# PiTopUSBHub.net
KiCad netlist of a schematic drawn in Altium Designer
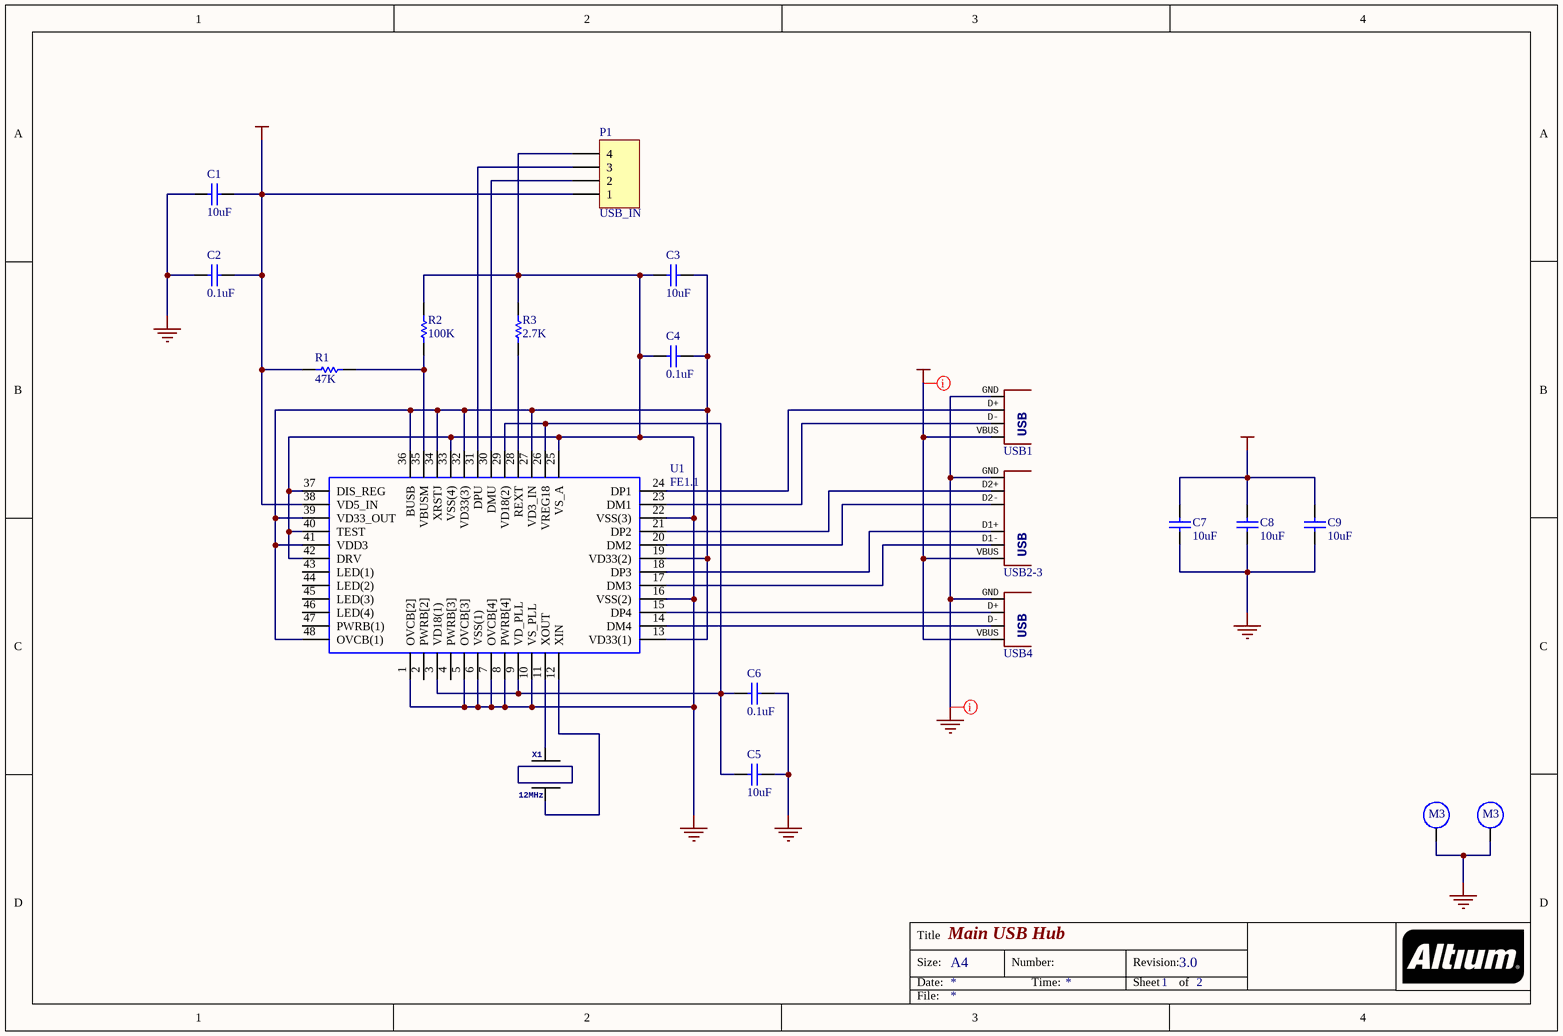
[diagram p0: PiTopUSBHub.SchDoc]

(export (version "E")
  (design (tool "Eeschema 10.0.6"))
  (components
    (comp (ref "C1")
      (value "10uF")
      (footprint "C0805")
      (description "Ceramic Chip Capacitor - Standard")
      (fields (field (name "Comment") "C0805") (field (name "PUBLISHER") "Altium Limited"))
      (libsource (lib "KEMET Chip Capacitor") (part "C0805"))
    )
    (comp (ref "C2")
      (value "0.1uF")
      (footprint "C0805")
      (description "Ceramic Chip Capacitor - Standard")
      (fields (field (name "Comment") "C0805") (field (name "PUBLISHER") "Altium Limited"))
      (libsource (lib "KEMET Chip Capacitor") (part "C0805"))
    )
    (comp (ref "C3")
      (value "10uF")
      (footprint "C0805")
      (description "Ceramic Chip Capacitor - Standard")
      (fields (field (name "Comment") "C0805") (field (name "PUBLISHER") "Altium Limited"))
      (libsource (lib "KEMET Chip Capacitor") (part "C0805"))
    )
    (comp (ref "C4")
      (value "0.1uF")
      (footprint "C0805")
      (description "Ceramic Chip Capacitor - Standard")
      (fields (field (name "Comment") "C0805") (field (name "PUBLISHER") "Altium Limited"))
      (libsource (lib "KEMET Chip Capacitor") (part "C0805"))
    )
    (comp (ref "C5")
      (value "10uF")
      (footprint "C0805")
      (description "Ceramic Chip Capacitor - Standard")
      (fields (field (name "Comment") "C0805") (field (name "PUBLISHER") "Altium Limited"))
      (libsource (lib "KEMET Chip Capacitor") (part "C0805"))
    )
    (comp (ref "C6")
      (value "0.1uF")
      (footprint "C0805")
      (description "Ceramic Chip Capacitor - Standard")
      (fields (field (name "Comment") "C0805") (field (name "PUBLISHER") "Altium Limited"))
      (libsource (lib "KEMET Chip Capacitor") (part "C0805"))
    )
    (comp (ref "C7")
      (value "10uF")
      (footprint "C0805")
      (description "Ceramic Chip Capacitor - Standard")
      (fields (field (name "Comment") "C0805") (field (name "PUBLISHER") "Altium Limited"))
      (libsource (lib "KEMET Chip Capacitor") (part "C0805"))
    )
    (comp (ref "C8")
      (value "10uF")
      (footprint "C0805")
      (description "Ceramic Chip Capacitor - Standard")
      (fields (field (name "Comment") "C0805") (field (name "PUBLISHER") "Altium Limited"))
      (libsource (lib "KEMET Chip Capacitor") (part "C0805"))
    )
    (comp (ref "C9")
      (value "10uF")
      (footprint "C0805")
      (description "Ceramic Chip Capacitor - Standard")
      (fields (field (name "Comment") "C0805") (field (name "PUBLISHER") "Altium Limited"))
      (libsource (lib "KEMET Chip Capacitor") (part "C0805"))
    )
    (comp (ref "H1") (value "M3") (footprint "M3") (libsource (lib "lib") (part "M3")))
    (comp (ref "H2") (value "M3") (footprint "M3") (libsource (lib "lib") (part "M3")))
    (comp (ref "P1")
      (value "USB_IN")
      (footprint "HDR1X4")
      (description "Header, 4-Pin")
      (fields (field (name "PUBLISHER") "Altium Limited"))
      (libsource (lib "Miscellaneous Connectors") (part "Header 4"))
    )
    (comp (ref "R1")
      (value "47K")
      (footprint "R0805")
      (fields (field (name "PUBLISHER") "Altium Limited"))
      (libsource (lib "lib") (part "R0805"))
    )
    (comp (ref "R2")
      (value "100K")
      (footprint "R0805")
      (fields (field (name "PUBLISHER") "Altium Limited"))
      (libsource (lib "lib") (part "R0805"))
    )
    (comp (ref "R3")
      (value "2.7K")
      (footprint "R0805")
      (fields (field (name "PUBLISHER") "Altium Limited"))
      (libsource (lib "lib") (part "R0805"))
    )
    (comp (ref "U1")
      (value "FE1.1")
      (footprint "LQFP48")
      (description "USB 2.0 HIGH SPEED 4-PORT HUB CONTROLLER")
      (libsource (lib "lib") (part "FE1.1"))
    )
    (comp (ref "USB1")
      (value "USBA-PTH")
      (footprint "USB-A-F-PTH")
      (fields (field (name "USB") "USB"))
      (libsource (lib "lib") (part "USBA-PTH"))
    )
    (comp (ref "USB2-3")
      (value "USBA2x-PTH")
      (footprint "USB-A-2x-F-PTH")
      (fields (field (name "USB") "USB"))
      (libsource (lib "lib") (part "USBA2x-PTH"))
    )
    (comp (ref "USB4")
      (value "USBA-PTH")
      (footprint "USB-A-F-PTH")
      (fields (field (name "USB") "USB"))
      (libsource (lib "lib") (part "USBA-PTH"))
    )
    (comp (ref "X1")
      (value "12MHz")
      (footprint "XTAL_G5032")
      (description "PTH: ...   SMD: ...   Cylinder: CMR200T-32.768KDZBT")
      (libsource (lib "lib") (part "CRYSTALHC49UP"))
    )
  )
  (nets
    (net (code "1") (name "GND") (class "Default")
      (node (ref "C1") (pin "2") (pinfunction "2_2") (pintype "passive"))
      (node (ref "C2") (pin "2") (pinfunction "2_2") (pintype "passive"))
      (node (ref "C3") (pin "2") (pinfunction "2_2") (pintype "passive"))
      (node (ref "C4") (pin "2") (pinfunction "2_2") (pintype "passive"))
      (node (ref "C5") (pin "2") (pinfunction "2_2") (pintype "passive"))
      (node (ref "C6") (pin "2") (pinfunction "2_2") (pintype "passive"))
      (node (ref "C7") (pin "2") (pinfunction "2_2") (pintype "passive"))
      (node (ref "C8") (pin "2") (pinfunction "2_2") (pintype "passive"))
      (node (ref "C9") (pin "2") (pinfunction "2_2") (pintype "passive"))
      (node (ref "H1") (pin "1") (pinfunction "1_1") (pintype "passive"))
      (node (ref "H2") (pin "1") (pinfunction "1_1") (pintype "passive"))
      (node (ref "P1") (pin "4") (pinfunction "4_4") (pintype "passive"))
      (node (ref "R2") (pin "1") (pinfunction "1_1") (pintype "passive"))
      (node (ref "R3") (pin "2") (pinfunction "2_2") (pintype "passive"))
      (node (ref "U1") (pin "1") (pinfunction "OVCB[2]_1") (pintype "passive"))
      (node (ref "U1") (pin "10") (pinfunction "VS_PLL_10") (pintype "passive"))
      (node (ref "U1") (pin "16") (pinfunction "VSS(2)_16") (pintype "passive"))
      (node (ref "U1") (pin "22") (pinfunction "VSS(3)_22") (pintype "passive"))
      (node (ref "U1") (pin "25") (pinfunction "VS_A_25") (pintype "passive"))
      (node (ref "U1") (pin "33") (pinfunction "VSS(4)_33") (pintype "passive"))
      (node (ref "U1") (pin "37") (pinfunction "DIS_REG_37") (pintype "passive"))
      (node (ref "U1") (pin "40") (pinfunction "TEST_40") (pintype "passive"))
      (node (ref "U1") (pin "42") (pinfunction "DRV_42") (pintype "passive"))
      (node (ref "U1") (pin "5") (pinfunction "OVCB[3]_5") (pintype "passive"))
      (node (ref "U1") (pin "6") (pinfunction "VSS(1)_6") (pintype "passive"))
      (node (ref "U1") (pin "7") (pinfunction "OVCB[4]_7") (pintype "passive"))
      (node (ref "U1") (pin "8") (pinfunction "PWRB[4]_8") (pintype "passive"))
      (node (ref "USB1") (pin "GND") (pinfunction "GND_GND") (pintype "passive"))
      (node (ref "USB2-3") (pin "GND") (pinfunction "GND_GND") (pintype "passive"))
      (node (ref "USB4") (pin "GND") (pinfunction "GND_GND") (pintype "passive"))
    )
    (net (code "2") (name "Net-(U1-BUSB)") (class "Default")
      (node (ref "C3") (pin "1") (pinfunction "1_1") (pintype "passive"))
      (node (ref "C4") (pin "1") (pinfunction "1_1") (pintype "passive"))
      (node (ref "U1") (pin "13") (pinfunction "VD33(1)_13") (pintype "passive"))
      (node (ref "U1") (pin "19") (pinfunction "VD33(2)_19") (pintype "passive"))
      (node (ref "U1") (pin "27") (pinfunction "VD3_IN_27") (pintype "passive"))
      (node (ref "U1") (pin "32") (pinfunction "VD33(3)_32") (pintype "passive"))
      (node (ref "U1") (pin "34") (pinfunction "XRSTJ_34") (pintype "passive"))
      (node (ref "U1") (pin "36") (pinfunction "BUSB_36") (pintype "passive"))
      (node (ref "U1") (pin "39") (pinfunction "VD33_OUT_39") (pintype "passive"))
      (node (ref "U1") (pin "41") (pinfunction "VDD3_41") (pintype "passive"))
      (node (ref "U1") (pin "48") (pinfunction "OVCB(1)_48") (pintype "passive"))
    )
    (net (code "3") (name "Net-(U1-DM1)") (class "Default")
      (node (ref "U1") (pin "23") (pinfunction "DM1_23") (pintype "passive"))
      (node (ref "USB1") (pin "D-") (pinfunction "D-_D-") (pintype "passive"))
    )
    (net (code "4") (name "Net-(U1-DM2)") (class "Default")
      (node (ref "U1") (pin "20") (pinfunction "DM2_20") (pintype "passive"))
      (node (ref "USB2-3") (pin "D2-") (pinfunction "D2-_D2-") (pintype "passive"))
    )
    (net (code "5") (name "Net-(U1-DM3)") (class "Default")
      (node (ref "U1") (pin "17") (pinfunction "DM3_17") (pintype "passive"))
      (node (ref "USB2-3") (pin "D1-") (pinfunction "D1-_D1-") (pintype "passive"))
    )
    (net (code "6") (name "Net-(U1-DM4)") (class "Default")
      (node (ref "U1") (pin "14") (pinfunction "DM4_14") (pintype "passive"))
      (node (ref "USB4") (pin "D-") (pinfunction "D-_D-") (pintype "passive"))
    )
    (net (code "7") (name "Net-(U1-DMU)") (class "Default")
      (node (ref "P1") (pin "2") (pinfunction "2_2") (pintype "passive"))
      (node (ref "U1") (pin "30") (pinfunction "DMU_30") (pintype "passive"))
    )
    (net (code "8") (name "Net-(U1-DP1)") (class "Default")
      (node (ref "U1") (pin "24") (pinfunction "DP1_24") (pintype "passive"))
      (node (ref "USB1") (pin "D+") (pinfunction "D+_D+") (pintype "passive"))
    )
    (net (code "9") (name "Net-(U1-DP2)") (class "Default")
      (node (ref "U1") (pin "21") (pinfunction "DP2_21") (pintype "passive"))
      (node (ref "USB2-3") (pin "D2+") (pinfunction "D2+_D2+") (pintype "passive"))
    )
    (net (code "10") (name "Net-(U1-DP3)") (class "Default")
      (node (ref "U1") (pin "18") (pinfunction "DP3_18") (pintype "passive"))
      (node (ref "USB2-3") (pin "D1+") (pinfunction "D1+_D1+") (pintype "passive"))
    )
    (net (code "11") (name "Net-(U1-DP4)") (class "Default")
      (node (ref "U1") (pin "15") (pinfunction "DP4_15") (pintype "passive"))
      (node (ref "USB4") (pin "D+") (pinfunction "D+_D+") (pintype "passive"))
    )
    (net (code "12") (name "Net-(U1-DPU)") (class "Default")
      (node (ref "P1") (pin "3") (pinfunction "3_3") (pintype "passive"))
      (node (ref "U1") (pin "31") (pinfunction "DPU_31") (pintype "passive"))
    )
    (net (code "13") (name "Net-(U1-REXT)") (class "Default")
      (node (ref "R3") (pin "1") (pinfunction "1_1") (pintype "passive"))
      (node (ref "U1") (pin "28") (pinfunction "REXT_28") (pintype "passive"))
    )
    (net (code "14") (name "Net-(U1-VBUSM)") (class "Default")
      (node (ref "R1") (pin "2") (pinfunction "2_2") (pintype "passive"))
      (node (ref "R2") (pin "2") (pinfunction "2_2") (pintype "passive"))
      (node (ref "U1") (pin "35") (pinfunction "VBUSM_35") (pintype "passive"))
    )
    (net (code "15") (name "Net-(U1-VD18(1))") (class "Default")
      (node (ref "C5") (pin "1") (pinfunction "1_1") (pintype "passive"))
      (node (ref "C6") (pin "1") (pinfunction "1_1") (pintype "passive"))
      (node (ref "U1") (pin "26") (pinfunction "VREG18_26") (pintype "passive"))
      (node (ref "U1") (pin "29") (pinfunction "VD18(2)_29") (pintype "passive"))
      (node (ref "U1") (pin "3") (pinfunction "VD18(1)_3") (pintype "passive"))
      (node (ref "U1") (pin "9") (pinfunction "VD_PLL_9") (pintype "passive"))
    )
    (net (code "16") (name "Net-(U1-XIN)") (class "Default")
      (node (ref "U1") (pin "12") (pinfunction "XIN_12") (pintype "passive"))
      (node (ref "X1") (pin "1") (pinfunction "1_1") (pintype "passive"))
    )
    (net (code "17") (name "Net-(U1-XOUT)") (class "Default")
      (node (ref "U1") (pin "11") (pinfunction "XOUT_11") (pintype "passive"))
      (node (ref "X1") (pin "2") (pinfunction "2_2") (pintype "passive"))
    )
    (net (code "18") (name "VCC") (class "Default")
      (node (ref "C1") (pin "1") (pinfunction "1_1") (pintype "passive"))
      (node (ref "C2") (pin "1") (pinfunction "1_1") (pintype "passive"))
      (node (ref "C7") (pin "1") (pinfunction "1_1") (pintype "passive"))
      (node (ref "C8") (pin "1") (pinfunction "1_1") (pintype "passive"))
      (node (ref "C9") (pin "1") (pinfunction "1_1") (pintype "passive"))
      (node (ref "P1") (pin "1") (pinfunction "1_1") (pintype "passive"))
      (node (ref "R1") (pin "1") (pinfunction "1_1") (pintype "passive"))
      (node (ref "U1") (pin "38") (pinfunction "VD5_IN_38") (pintype "passive"))
      (node (ref "USB1") (pin "VBUS") (pinfunction "VBUS_VBUS") (pintype "passive"))
      (node (ref "USB2-3") (pin "VBUS") (pinfunction "VBUS_VBUS") (pintype "passive"))
      (node (ref "USB4") (pin "VBUS") (pinfunction "VBUS_VBUS") (pintype "passive"))
    )
    (net (code "19") (name "unconnected-(U1-LED(1)-Pad43)") (class "Default")
      (node (ref "U1") (pin "43") (pinfunction "LED(1)_43") (pintype "passive"))
    )
    (net (code "20") (name "unconnected-(U1-LED(2)-Pad44)") (class "Default")
      (node (ref "U1") (pin "44") (pinfunction "LED(2)_44") (pintype "passive"))
    )
    (net (code "21") (name "unconnected-(U1-LED(3)-Pad45)") (class "Default")
      (node (ref "U1") (pin "45") (pinfunction "LED(3)_45") (pintype "passive"))
    )
    (net (code "22") (name "unconnected-(U1-LED(4)-Pad46)") (class "Default")
      (node (ref "U1") (pin "46") (pinfunction "LED(4)_46") (pintype "passive"))
    )
    (net (code "23") (name "unconnected-(U1-PWRB(1)-Pad47)") (class "Default")
      (node (ref "U1") (pin "47") (pinfunction "PWRB(1)_47") (pintype "passive"))
    )
    (net (code "24") (name "unconnected-(U1-PWRB[2]-Pad2)") (class "Default")
      (node (ref "U1") (pin "2") (pinfunction "PWRB[2]_2") (pintype "passive"))
    )
    (net (code "25") (name "unconnected-(U1-PWRB[3]-Pad4)") (class "Default")
      (node (ref "U1") (pin "4") (pinfunction "PWRB[3]_4") (pintype "passive"))
    )
  )
)
